# AuxSupply_USB.net
KiCad netlist of a schematic drawn in Altium Designer
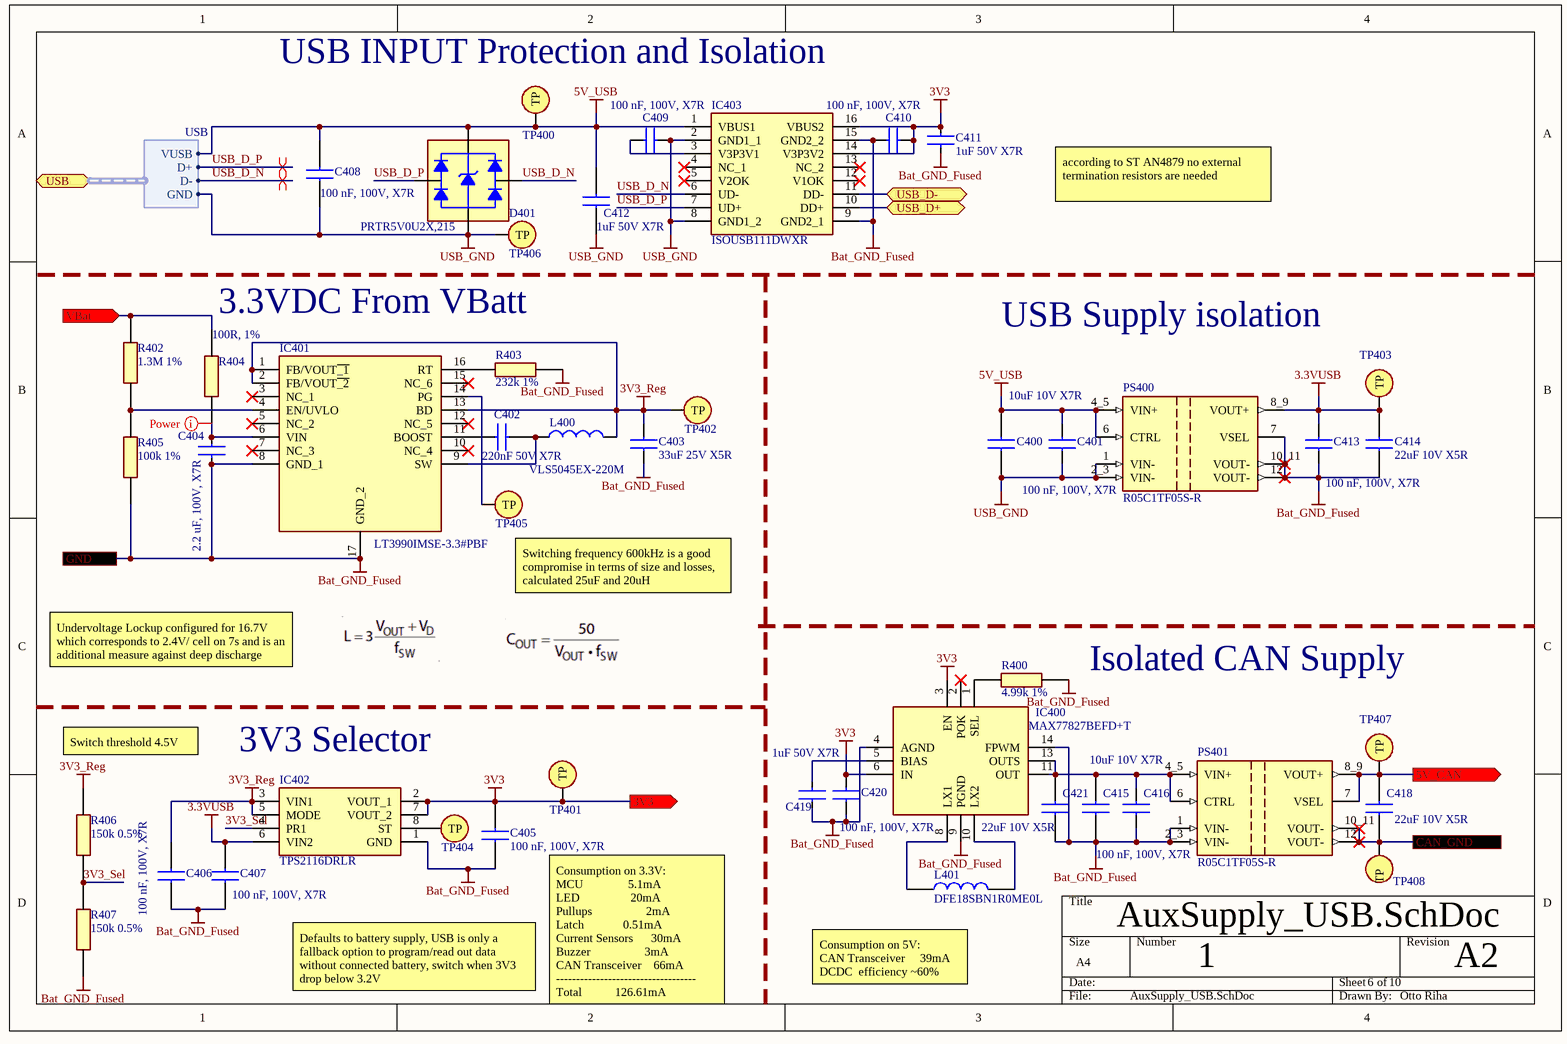
[diagram p0: AuxSupply_USB.SchDoc]

(export (version "E")
  (design (tool "Eeschema 10.0.6"))
  (components
    (comp (ref "C400")
      (value "10uF 10V X7R")
      (footprint "SamacSys:GRM18x")
      (description "Capacitor")
      (fields
        (field (name "MANUFACTURER_PART_NUMBER") "GRM188Z71A106MA73D")
        (field (name "MOUSER PART NUMBER") "81-GRM188Z71A106MA3D")
      )
      (libsource (lib "*") (part "GRM188Z71A106MA73D"))
    )
    (comp (ref "C401")
      (value "100 nF, 100V, X7R")
      (footprint "SamacSys:MAJx16")
      (description "Capacitor 100nF, 100V, X7R")
      (fields
        (field (name "MANUFACTURER_PART_NUMBER") "MAJCH168BB7104KTEA01")
        (field (name "MOUSER PART NUMBER") "963-MAJCH168BB7104KT")
      )
      (libsource (lib "SamacSys") (part "MAJCH168BB7104KTEA01"))
    )
    (comp (ref "C402")
      (value "220nF 50V X7R")
      (footprint "SamacSys:GRM18x")
      (description "Capacitor")
      (fields
        (field (name "MANUFACTURER_PART_NUMBER") "GRM188R71H224KAC4J")
        (field (name "MOUSER PART NUMBER") "81-GRM188R71H224KA4J")
      )
      (libsource (lib "*") (part "GRM188R71H224KAC4J"))
    )
    (comp (ref "C403")
      (value "33uF 25V X5R")
      (footprint "SamacSys:CAPC3216X180N")
      (description "Capacitor 33uF 25V X5R")
      (fields
        (field (name "MANUFACTURER_PART_NUMBER") "C3216X5R1E336M160AC")
        (field (name "MOUSER PART NUMBER") "810-C3216X5R1E336M")
      )
      (libsource (lib "SamacSys") (part "C3216X5R1E336M160AC"))
    )
    (comp (ref "C404")
      (value "2.2 uF, 100V, X7R")
      (footprint "SamacSys:CAPC2012X145N")
      (description "Capacitor 2.2 uF, 100V, X7R")
      (fields
        (field (name "MANUFACTURER_PART_NUMBER") "C2012X7R2A225K125AC")
        (field (name "MOUSER PART NUMBER") "810-C2012X7R2225K125")
      )
      (libsource (lib "SamacSys") (part "C2012X7R2A225K125AC"))
    )
    (comp (ref "C405")
      (value "100 nF, 100V, X7R")
      (footprint "SamacSys:MAJx16")
      (description "Capacitor 100nF, 100V, X7R")
      (fields
        (field (name "MANUFACTURER_PART_NUMBER") "MAJCH168BB7104KTEA01")
        (field (name "MOUSER PART NUMBER") "963-MAJCH168BB7104KT")
      )
      (libsource (lib "") (part "MAJCH168BB7104KTEA01_1"))
    )
    (comp (ref "C406")
      (value "100 nF, 100V, X7R")
      (footprint "SamacSys:MAJx16")
      (description "Capacitor 100nF, 100V, X7R")
      (fields
        (field (name "MANUFACTURER_PART_NUMBER") "MAJCH168BB7104KTEA01")
        (field (name "MOUSER PART NUMBER") "963-MAJCH168BB7104KT")
      )
      (libsource (lib "") (part "MAJCH168BB7104KTEA01_1"))
    )
    (comp (ref "C407")
      (value "100 nF, 100V, X7R")
      (footprint "SamacSys:MAJx16")
      (description "Capacitor 100nF, 100V, X7R")
      (fields
        (field (name "MANUFACTURER_PART_NUMBER") "MAJCH168BB7104KTEA01")
        (field (name "MOUSER PART NUMBER") "963-MAJCH168BB7104KT")
      )
      (libsource (lib "") (part "MAJCH168BB7104KTEA01_1"))
    )
    (comp (ref "C408")
      (value "100 nF, 100V, X7R")
      (footprint "SamacSys:MAJx16")
      (description "Capacitor 100nF, 100V, X7R")
      (fields
        (field (name "MANUFACTURER_PART_NUMBER") "MAJCH168BB7104KTEA01")
        (field (name "MOUSER PART NUMBER") "963-MAJCH168BB7104KT")
      )
      (libsource (lib "") (part "MAJCH168BB7104KTEA01_1"))
    )
    (comp (ref "C409")
      (value "100 nF, 100V, X7R")
      (footprint "SamacSys:MAJx16")
      (description "Capacitor 100nF, 100V, X7R")
      (fields
        (field (name "MANUFACTURER_PART_NUMBER") "MAJCH168BB7104KTEA01")
        (field (name "MOUSER PART NUMBER") "963-MAJCH168BB7104KT")
      )
      (libsource (lib "SamacSys") (part "MAJCH168BB7104KTEA01"))
    )
    (comp (ref "C410")
      (value "100 nF, 100V, X7R")
      (footprint "SamacSys:MAJx16")
      (description "Capacitor 100nF, 100V, X7R")
      (fields
        (field (name "MANUFACTURER_PART_NUMBER") "MAJCH168BB7104KTEA01")
        (field (name "MOUSER PART NUMBER") "963-MAJCH168BB7104KT")
      )
      (libsource (lib "SamacSys") (part "MAJCH168BB7104KTEA01"))
    )
    (comp (ref "C411")
      (value "1uF 50V X7R")
      (footprint "SamacSys:CAPC1608X90N")
      (description "Capacitor 1uF 50V X7R")
      (fields
        (field (name "MANUFACTURER_PART_NUMBER") "06035C105MAT2A")
        (field (name "MOUSER PART NUMBER") "581-06035C105MAT2A")
      )
      (libsource (lib "SamacSys") (part "06035C105MAT2A"))
    )
    (comp (ref "C412")
      (value "1uF 50V X7R")
      (footprint "SamacSys:CAPC1608X90N")
      (description "Capacitor 1uF 50V X7R")
      (fields
        (field (name "MANUFACTURER_PART_NUMBER") "06035C105MAT2A")
        (field (name "MOUSER PART NUMBER") "581-06035C105MAT2A")
      )
      (libsource (lib "") (part "06035C105MAT2A_1"))
    )
    (comp (ref "C413")
      (value "100 nF, 100V, X7R")
      (footprint "SamacSys:MAJx16")
      (description "Capacitor 100nF, 100V, X7R")
      (fields
        (field (name "MANUFACTURER_PART_NUMBER") "MAJCH168BB7104KTEA01")
        (field (name "MOUSER PART NUMBER") "963-MAJCH168BB7104KT")
      )
      (libsource (lib "SamacSys") (part "MAJCH168BB7104KTEA01"))
    )
    (comp (ref "C414")
      (value "22uF 10V X5R")
      (footprint "SamacSys:CAPC1608X105N")
      (description "Capacitor")
      (fields
        (field (name "MANUFACTURER_PART_NUMBER") "CL10A226MP8NUNE")
        (field (name "MOUSER PART NUMBER") "187-CL10A226MP8NUNE")
      )
      (libsource (lib "*") (part "CL10A226MP8NUNE"))
    )
    (comp (ref "C415")
      (value "10uF 10V X7R")
      (footprint "SamacSys:GRM18x")
      (description "Capacitor")
      (fields
        (field (name "MANUFACTURER_PART_NUMBER") "GRM188Z71A106MA73D")
        (field (name "MOUSER PART NUMBER") "81-GRM188Z71A106MA3D")
      )
      (libsource (lib "*") (part "GRM188Z71A106MA73D"))
    )
    (comp (ref "C416")
      (value "100 nF, 100V, X7R")
      (footprint "SamacSys:MAJx16")
      (description "Capacitor 100nF, 100V, X7R")
      (fields
        (field (name "MANUFACTURER_PART_NUMBER") "MAJCH168BB7104KTEA01")
        (field (name "MOUSER PART NUMBER") "963-MAJCH168BB7104KT")
      )
      (libsource (lib "SamacSys") (part "MAJCH168BB7104KTEA01"))
    )
    (comp (ref "C418")
      (value "22uF 10V X5R")
      (footprint "SamacSys:CAPC1608X105N")
      (description "Capacitor")
      (fields
        (field (name "MANUFACTURER_PART_NUMBER") "CL10A226MP8NUNE")
        (field (name "MOUSER PART NUMBER") "187-CL10A226MP8NUNE")
      )
      (libsource (lib "*") (part "CL10A226MP8NUNE"))
    )
    (comp (ref "C419")
      (value "1uF 50V X7R")
      (footprint "SamacSys:CAPC1608X90N")
      (description "Capacitor 1uF 50V X7R")
      (fields
        (field (name "MANUFACTURER_PART_NUMBER") "06035C105MAT2A")
        (field (name "MOUSER PART NUMBER") "581-06035C105MAT2A")
      )
      (libsource (lib "SamacSys") (part "06035C105MAT2A"))
    )
    (comp (ref "C420")
      (value "100 nF, 100V, X7R")
      (footprint "SamacSys:MAJx16")
      (description "Capacitor 100nF, 100V, X7R")
      (fields
        (field (name "MANUFACTURER_PART_NUMBER") "MAJCH168BB7104KTEA01")
        (field (name "MOUSER PART NUMBER") "963-MAJCH168BB7104KT")
      )
      (libsource (lib "SamacSys") (part "MAJCH168BB7104KTEA01"))
    )
    (comp (ref "C421")
      (value "22uF 10V X5R")
      (footprint "SamacSys:CAPC1608X105N")
      (description "Capacitor")
      (fields
        (field (name "MANUFACTURER_PART_NUMBER") "CL10A226MP8NUNE")
        (field (name "MOUSER PART NUMBER") "187-CL10A226MP8NUNE")
      )
      (libsource (lib "*") (part "CL10A226MP8NUNE"))
    )
    (comp (ref "D401")
      (value "PRTR5V0U2X,215")
      (footprint "SamacSys:PRTR5V0U2X")
      (description "Diode")
      (fields (field (name "MOUSER PART NUMBER") "771-PRTR5V0U2X-T/R"))
      (libsource (lib "SamacSys") (part "PRTR5V0U2X,215"))
    )
    (comp (ref "IC400")
      (value "MAX77827BEFD+T")
      (footprint "SamacSys:MAX77827BEFDT")
      (description "Integrated Circuit")
      (fields (field (name "MOUSER PART NUMBER") "700-MAX77827BEFD+T"))
      (libsource (lib "*") (part "MAX77827BEFD+T"))
    )
    (comp (ref "IC401")
      (value "LT3990IMSE-3.3#PBF")
      (footprint "SamacSys:SOP50P490X110-17N")
      (description "Integrated Circuit")
      (fields (field (name "MOUSER PART NUMBER") "584-3990IMSE-3.3PBF"))
      (libsource (lib "*") (part "LT3990IMSE-3.3#PBF"))
    )
    (comp (ref "IC402")
      (value "TPS2116DRLR")
      (footprint "SamacSys:SOTFL50P160X60-8N")
      (description "Integrated Circuit")
      (fields (field (name "MOUSER PART NUMBER") "595-TPS2116DRLR"))
      (libsource (lib "SamacSys") (part "TPS2116DRLR"))
    )
    (comp (ref "IC403")
      (value "ISOUSB111DWXR")
      (footprint "SamacSys:SOP65P1030X260-16N")
      (description "Integrated Circuit")
      (fields (field (name "MOUSER PART NUMBER") "595-ISOUSB111DWXR"))
      (libsource (lib "*") (part "ISOUSB111DWXR"))
    )
    (comp (ref "L400")
      (value "VLS5045EX-220M")
      (footprint "SamacSys:VLS5045EX330M")
      (description "Inductor")
      (fields (field (name "MOUSER PART NUMBER") "810-VLS5045EX-220M"))
      (libsource (lib "*") (part "VLS5045EX-220M"))
    )
    (comp (ref "L401")
      (value "DFE18SBN1R0ME0L")
      (footprint "SamacSys:DFE18SAN1R0ME0L")
      (description "Inductor")
      (fields (field (name "MOUSER PART NUMBER") "81-DFE18SBN1R0ME0L"))
      (libsource (lib "*") (part "DFE18SBN1R0ME0L"))
    )
    (comp (ref "PS400")
      (value "R05C1TF05S-R")
      (footprint "CONV_R05C1TF05S-R")
      (fields (field (name "MF") "{'manufacturer': u'Recom Power'}"))
      (libsource (lib "R05C1TF05S-R") (part "R05C1TF05S-R"))
    )
    (comp (ref "PS401")
      (value "R05C1TF05S-R")
      (footprint "CONV_R05C1TF05S-R")
      (fields (field (name "MF") "{'manufacturer': u'Recom Power'}"))
      (libsource (lib "R05C1TF05S-R") (part "R05C1TF05S-R"))
    )
    (comp (ref "R400")
      (value "4.99k 1%")
      (footprint "SamacSys:RESC0603X26N")
      (description "Resistor")
      (fields
        (field (name "MANUFACTURER_PART_NUMBER") "CR0201-FW-4991GLF")
        (field (name "MOUSER PART NUMBER") "652-CR0201FW-4991GLF")
      )
      (libsource (lib "*") (part "CR0201-FW-4991GLF"))
    )
    (comp (ref "R402")
      (value "1.3M 1%")
      (footprint "SamacSys:RESC1608X55N")
      (description "Resistor 1.3M 1%")
      (fields
        (field (name "MANUFACTURER_PART_NUMBER") "MCT0603MD1304BP500")
        (field (name "MOUSER PART NUMBER") "594-MCT0603MD1304BP5")
      )
      (libsource (lib "SamacSys") (part "MCT0603MD1304BP500"))
    )
    (comp (ref "R403")
      (value "232k 1%")
      (footprint "SamacSys:RESC1608X50N")
      (description "Resistor")
      (fields
        (field (name "MANUFACTURER_PART_NUMBER") "CRCW0603232KFKEA")
        (field (name "MOUSER PART NUMBER") "71-CRCW0603-232K-E3")
      )
      (libsource (lib "*") (part "CRCW0603232KFKEA"))
    )
    (comp (ref "R404")
      (value "100R, 1%")
      (footprint "SamacSys:RESC1608X50N")
      (description "Resistor 100R, 1%")
      (fields
        (field (name "MANUFACTURER_PART_NUMBER") "CRCW0603100RFKEA")
        (field (name "MOUSER PART NUMBER") "71-CRCW0603-100-E3")
      )
      (libsource (lib "SamacSys") (part "CRCW0603100RFKEA"))
    )
    (comp (ref "R405")
      (value "100k 1%")
      (footprint "SamacSys:RESC1608X55N")
      (description "Resistor 100k, 1%")
      (fields
        (field (name "MANUFACTURER_PART_NUMBER") "CRCW0603100KFKEAC")
        (field (name "MOUSER PART NUMBER") "71-CRCW0603100KFKEAC")
      )
      (libsource (lib "SamacSys") (part "CRCW0603100KFKEAC"))
    )
    (comp (ref "R406")
      (value "150k 0.5%")
      (footprint "SamacSys:ERA3AEB101V")
      (description "Resistor 150k 0.5%")
      (fields
        (field (name "MANUFACTURER_PART_NUMBER") "ERA-3AED154V")
        (field (name "MOUSER PART NUMBER") "667-ERA-3AED154V")
      )
      (libsource (lib "SamacSys") (part "ERA-3AED154V"))
    )
    (comp (ref "R407")
      (value "150k 0.5%")
      (footprint "SamacSys:ERA3AEB101V")
      (description "Resistor 150k 0.5%")
      (fields
        (field (name "MANUFACTURER_PART_NUMBER") "ERA-3AED154V")
        (field (name "MOUSER PART NUMBER") "667-ERA-3AED154V")
      )
      (libsource (lib "SamacSys") (part "ERA-3AED154V"))
    )
    (comp (ref "TP400")
      (value "Testpoint")
      (footprint "Testpoint")
      (libsource (lib "SamacSys") (part "Testpoint"))
    )
    (comp (ref "TP401")
      (value "Testpoint")
      (footprint "Testpoint")
      (libsource (lib "SamacSys") (part "Testpoint"))
    )
    (comp (ref "TP402")
      (value "Testpoint")
      (footprint "Testpoint")
      (libsource (lib "SamacSys") (part "Testpoint"))
    )
    (comp (ref "TP403")
      (value "Testpoint")
      (footprint "Testpoint")
      (libsource (lib "SamacSys") (part "Testpoint"))
    )
    (comp (ref "TP404")
      (value "Testpoint")
      (footprint "Testpoint")
      (libsource (lib "SamacSys") (part "Testpoint"))
    )
    (comp (ref "TP405")
      (value "Testpoint")
      (footprint "Testpoint")
      (libsource (lib "SamacSys") (part "Testpoint"))
    )
    (comp (ref "TP406")
      (value "Testpoint")
      (footprint "Testpoint")
      (libsource (lib "SamacSys") (part "Testpoint"))
    )
    (comp (ref "TP407")
      (value "Testpoint")
      (footprint "Testpoint")
      (libsource (lib "SamacSys") (part "Testpoint"))
    )
    (comp (ref "TP408")
      (value "Testpoint")
      (footprint "Testpoint")
      (libsource (lib "SamacSys") (part "Testpoint"))
    )
  )
  (nets
    (net (code "2") (name "/3V3_Sel") (class "Default")
      (node (ref "IC402") (pin "4") (pinfunction "PR1_4") (pintype "passive"))
      (node (ref "R406") (pin "1") (pinfunction "1_1") (pintype "passive"))
      (node (ref "R407") (pin "2") (pinfunction "2_2") (pintype "passive"))
    )
    (net (code "3") (name "/5V_CAN") (class "Default")
      (node (ref "C418") (pin "2") (pinfunction "2_2") (pintype "passive"))
      (node (ref "PS401") (pin "7") (pinfunction "VSEL_7") (pintype "passive"))
      (node (ref "PS401") (pin "8_9") (pinfunction "VOUT+_8_9") (pintype "output"))
      (node (ref "TP407") (pin "1") (pinfunction "TP_1") (pintype "passive"))
    )
    (net (code "4") (name "/CAN_GND") (class "Default")
      (node (ref "C418") (pin "1") (pinfunction "1_1") (pintype "passive"))
      (node (ref "PS401") (pin "10_11") (pinfunction "VOUT-_10_11") (pintype "output"))
      (node (ref "PS401") (pin "12") (pinfunction "VOUT-_12") (pintype "output"))
      (node (ref "TP408") (pin "1") (pinfunction "TP_1") (pintype "passive"))
    )
    (net (code "5") (name "/USB_D+") (class "Default")
      (node (ref "IC403") (pin "10") (pinfunction "DD+_10") (pintype "passive"))
    )
    (net (code "6") (name "/USB_D-") (class "Default")
      (node (ref "IC403") (pin "11") (pinfunction "DD-_11") (pintype "passive"))
    )
    (net (code "7") (name "/USB_D_N") (class "Default")
      (node (ref "D401") (pin "3") (pinfunction "input/output_2_3") (pintype "passive"))
      (node (ref "IC403") (pin "6") (pinfunction "UD-_6") (pintype "passive"))
    )
    (net (code "8") (name "/USB_D_P") (class "Default")
      (node (ref "D401") (pin "2") (pinfunction "input/output_1_2") (pintype "passive"))
      (node (ref "IC403") (pin "7") (pinfunction "UD+_7") (pintype "passive"))
    )
    (net (code "9") (name "/VBat") (class "Default")
      (node (ref "R402") (pin "2") (pinfunction "2_2") (pintype "passive"))
      (node (ref "R404") (pin "2") (pinfunction "2_2") (pintype "passive"))
    )
    (net (code "11") (name "3.3VUSB") (class "Default")
      (node (ref "C407") (pin "2") (pinfunction "2_2") (pintype "passive"))
      (node (ref "C413") (pin "1") (pinfunction "1_1") (pintype "passive"))
      (node (ref "C414") (pin "2") (pinfunction "2_2") (pintype "passive"))
      (node (ref "IC402") (pin "6") (pinfunction "VIN2_6") (pintype "passive"))
      (node (ref "PS400") (pin "8_9") (pinfunction "VOUT+_8_9") (pintype "output"))
      (node (ref "TP403") (pin "1") (pinfunction "TP_1") (pintype "passive"))
    )
    (net (code "12") (name "3V3") (class "Default")
      (node (ref "C405") (pin "2") (pinfunction "2_2") (pintype "passive"))
      (node (ref "C410") (pin "1") (pinfunction "1_1") (pintype "passive"))
      (node (ref "C411") (pin "2") (pinfunction "2_2") (pintype "passive"))
      (node (ref "C420") (pin "1") (pinfunction "1_1") (pintype "passive"))
      (node (ref "IC400") (pin "3") (pinfunction "EN_3") (pintype "passive"))
      (node (ref "IC400") (pin "6") (pinfunction "IN_6") (pintype "passive"))
      (node (ref "IC402") (pin "2") (pinfunction "VOUT_1_2") (pintype "passive"))
      (node (ref "IC402") (pin "7") (pinfunction "VOUT_2_7") (pintype "passive"))
      (node (ref "IC403") (pin "14") (pinfunction "V3P3V2_14") (pintype "passive"))
      (node (ref "IC403") (pin "16") (pinfunction "VBUS2_16") (pintype "passive"))
      (node (ref "TP401") (pin "1") (pinfunction "TP_1") (pintype "passive"))
    )
    (net (code "13") (name "3V3_Reg") (class "Default")
      (node (ref "C403") (pin "2") (pinfunction "2_2") (pintype "passive"))
      (node (ref "C406") (pin "2") (pinfunction "2_2") (pintype "passive"))
      (node (ref "IC401") (pin "1") (pinfunction "FB/VOUT~{_1}_1") (pintype "passive"))
      (node (ref "IC401") (pin "13") (pinfunction "BD_13") (pintype "passive"))
      (node (ref "IC401") (pin "2") (pinfunction "FB/VOUT~{_2}_2") (pintype "passive"))
      (node (ref "IC402") (pin "3") (pinfunction "VIN1_3") (pintype "passive"))
      (node (ref "IC402") (pin "5") (pinfunction "MODE_5") (pintype "passive"))
      (node (ref "L400") (pin "2") (pinfunction "2_2") (pintype "passive"))
      (node (ref "R406") (pin "2") (pinfunction "2_2") (pintype "passive"))
      (node (ref "TP402") (pin "1") (pinfunction "TP_1") (pintype "passive"))
    )
    (net (code "14") (name "5V_USB") (class "Default")
      (node (ref "C400") (pin "2") (pinfunction "2_2") (pintype "passive"))
      (node (ref "C401") (pin "1") (pinfunction "1_1") (pintype "passive"))
      (node (ref "C408") (pin "2") (pinfunction "2_2") (pintype "passive"))
      (node (ref "C412") (pin "1") (pinfunction "1_1") (pintype "passive"))
      (node (ref "D401") (pin "4") (pinfunction "supply_voltage_4") (pintype "passive"))
      (node (ref "IC403") (pin "1") (pinfunction "VBUS1_1") (pintype "passive"))
      (node (ref "PS400") (pin "4_5") (pinfunction "VIN+_4_5") (pintype "input"))
      (node (ref "PS400") (pin "6") (pinfunction "CTRL_6") (pintype "input"))
      (node (ref "TP400") (pin "1") (pinfunction "TP_1") (pintype "passive"))
    )
    (net (code "15") (name "Bat_GND_Fused") (class "Default")
      (node (ref "C403") (pin "1") (pinfunction "1_1") (pintype "passive"))
      (node (ref "C404") (pin "1") (pinfunction "1_1") (pintype "passive"))
      (node (ref "C405") (pin "1") (pinfunction "1_1") (pintype "passive"))
      (node (ref "C406") (pin "1") (pinfunction "1_1") (pintype "passive"))
      (node (ref "C407") (pin "1") (pinfunction "1_1") (pintype "passive"))
      (node (ref "C410") (pin "2") (pinfunction "2_2") (pintype "passive"))
      (node (ref "C411") (pin "1") (pinfunction "1_1") (pintype "passive"))
      (node (ref "C413") (pin "2") (pinfunction "2_2") (pintype "passive"))
      (node (ref "C414") (pin "1") (pinfunction "1_1") (pintype "passive"))
      (node (ref "C415") (pin "1") (pinfunction "1_1") (pintype "passive"))
      (node (ref "C416") (pin "2") (pinfunction "2_2") (pintype "passive"))
      (node (ref "C419") (pin "1") (pinfunction "1_1") (pintype "passive"))
      (node (ref "C420") (pin "2") (pinfunction "2_2") (pintype "passive"))
      (node (ref "C421") (pin "1") (pinfunction "1_1") (pintype "passive"))
      (node (ref "IC400") (pin "14") (pinfunction "FPWM_14") (pintype "passive"))
      (node (ref "IC400") (pin "4") (pinfunction "AGND_4") (pintype "passive"))
      (node (ref "IC400") (pin "9") (pinfunction "PGND_9") (pintype "passive"))
      (node (ref "IC401") (pin "17") (pinfunction "GND_2_17") (pintype "passive"))
      (node (ref "IC401") (pin "8") (pinfunction "GND_1_8") (pintype "passive"))
      (node (ref "IC402") (pin "1") (pinfunction "GND_1") (pintype "passive"))
      (node (ref "IC403") (pin "15") (pinfunction "GND2_2_15") (pintype "passive"))
      (node (ref "IC403") (pin "9") (pinfunction "GND2_1_9") (pintype "passive"))
      (node (ref "PS400") (pin "10_11") (pinfunction "VOUT-_10_11") (pintype "output"))
      (node (ref "PS400") (pin "12") (pinfunction "VOUT-_12") (pintype "output"))
      (node (ref "PS400") (pin "7") (pinfunction "VSEL_7") (pintype "passive"))
      (node (ref "PS401") (pin "1") (pinfunction "VIN-_1") (pintype "input"))
      (node (ref "PS401") (pin "2_3") (pinfunction "VIN-_2_3") (pintype "input"))
      (node (ref "R400") (pin "2") (pinfunction "2_2") (pintype "passive"))
      (node (ref "R403") (pin "2") (pinfunction "2_2") (pintype "passive"))
      (node (ref "R405") (pin "1") (pinfunction "1_1") (pintype "passive"))
      (node (ref "R407") (pin "1") (pinfunction "1_1") (pintype "passive"))
    )
    (net (code "16") (name "Net-(IC400-BIAS)") (class "Default")
      (node (ref "C419") (pin "2") (pinfunction "2_2") (pintype "passive"))
      (node (ref "IC400") (pin "5") (pinfunction "BIAS_5") (pintype "passive"))
    )
    (net (code "17") (name "Net-(IC400-LX1)") (class "Default")
      (node (ref "IC400") (pin "8") (pinfunction "LX1_8") (pintype "passive"))
      (node (ref "L401") (pin "1") (pinfunction "1_1") (pintype "passive"))
    )
    (net (code "18") (name "Net-(IC400-LX2)") (class "Default")
      (node (ref "IC400") (pin "10") (pinfunction "LX2_10") (pintype "passive"))
      (node (ref "L401") (pin "2") (pinfunction "2_2") (pintype "passive"))
    )
    (net (code "19") (name "Net-(IC400-OUT)") (class "Default")
      (node (ref "C415") (pin "2") (pinfunction "2_2") (pintype "passive"))
      (node (ref "C416") (pin "1") (pinfunction "1_1") (pintype "passive"))
      (node (ref "C421") (pin "2") (pinfunction "2_2") (pintype "passive"))
      (node (ref "IC400") (pin "11") (pinfunction "OUT_11") (pintype "passive"))
      (node (ref "IC400") (pin "13") (pinfunction "OUTS_13") (pintype "passive"))
      (node (ref "PS401") (pin "4_5") (pinfunction "VIN+_4_5") (pintype "input"))
      (node (ref "PS401") (pin "6") (pinfunction "CTRL_6") (pintype "input"))
    )
    (net (code "20") (name "Net-(IC400-SEL)") (class "Default")
      (node (ref "IC400") (pin "1") (pinfunction "SEL_1") (pintype "passive"))
      (node (ref "R400") (pin "1") (pinfunction "1_1") (pintype "passive"))
    )
    (net (code "21") (name "Net-(IC401-BOOST)") (class "Default")
      (node (ref "C402") (pin "1") (pinfunction "1_1") (pintype "passive"))
      (node (ref "IC401") (pin "11") (pinfunction "BOOST_11") (pintype "passive"))
    )
    (net (code "22") (name "Net-(IC401-EN{slash}UVLO)") (class "Default")
      (node (ref "IC401") (pin "4") (pinfunction "EN/UVLO_4") (pintype "passive"))
      (node (ref "R402") (pin "1") (pinfunction "1_1") (pintype "passive"))
      (node (ref "R405") (pin "2") (pinfunction "2_2") (pintype "passive"))
    )
    (net (code "23") (name "Net-(IC401-PG)") (class "Default")
      (node (ref "IC401") (pin "14") (pinfunction "PG_14") (pintype "passive"))
      (node (ref "TP405") (pin "1") (pinfunction "TP_1") (pintype "passive"))
    )
    (net (code "24") (name "Net-(IC401-RT)") (class "Default")
      (node (ref "IC401") (pin "16") (pinfunction "RT_16") (pintype "passive"))
      (node (ref "R403") (pin "1") (pinfunction "1_1") (pintype "passive"))
    )
    (net (code "25") (name "Net-(IC401-SW)") (class "Default")
      (node (ref "C402") (pin "2") (pinfunction "2_2") (pintype "passive"))
      (node (ref "IC401") (pin "9") (pinfunction "SW_9") (pintype "passive"))
      (node (ref "L400") (pin "1") (pinfunction "1_1") (pintype "passive"))
    )
    (net (code "26") (name "Net-(IC401-VIN)") (class "Default")
      (node (ref "C404") (pin "2") (pinfunction "2_2") (pintype "passive"))
      (node (ref "IC401") (pin "6") (pinfunction "VIN_6") (pintype "passive"))
      (node (ref "R404") (pin "1") (pinfunction "1_1") (pintype "passive"))
    )
    (net (code "27") (name "Net-(IC402-ST)") (class "Default")
      (node (ref "IC402") (pin "8") (pinfunction "ST_8") (pintype "passive"))
      (node (ref "TP404") (pin "1") (pinfunction "TP_1") (pintype "passive"))
    )
    (net (code "28") (name "Net-(IC403-V3P3V1)") (class "Default")
      (node (ref "C409") (pin "2") (pinfunction "2_2") (pintype "passive"))
      (node (ref "IC403") (pin "3") (pinfunction "V3P3V1_3") (pintype "passive"))
    )
    (net (code "29") (name "USB_GND") (class "Default")
      (node (ref "C400") (pin "1") (pinfunction "1_1") (pintype "passive"))
      (node (ref "C401") (pin "2") (pinfunction "2_2") (pintype "passive"))
      (node (ref "C408") (pin "1") (pinfunction "1_1") (pintype "passive"))
      (node (ref "C409") (pin "1") (pinfunction "1_1") (pintype "passive"))
      (node (ref "C412") (pin "2") (pinfunction "2_2") (pintype "passive"))
      (node (ref "D401") (pin "1") (pinfunction "ground_1") (pintype "passive"))
      (node (ref "IC403") (pin "2") (pinfunction "GND1_1_2") (pintype "passive"))
      (node (ref "IC403") (pin "8") (pinfunction "GND1_2_8") (pintype "passive"))
      (node (ref "PS400") (pin "1") (pinfunction "VIN-_1") (pintype "input"))
      (node (ref "PS400") (pin "2_3") (pinfunction "VIN-_2_3") (pintype "input"))
      (node (ref "TP406") (pin "1") (pinfunction "TP_1") (pintype "passive"))
    )
    (net (code "30") (name "unconnected-(IC400-POK-Pad2)") (class "Default")
      (node (ref "IC400") (pin "2") (pinfunction "POK_2") (pintype "passive+no_connect"))
    )
    (net (code "31") (name "unconnected-(IC401-NC_1-Pad3)") (class "Default")
      (node (ref "IC401") (pin "3") (pinfunction "NC_1_3") (pintype "passive+no_connect"))
    )
    (net (code "32") (name "unconnected-(IC401-NC_2-Pad5)") (class "Default")
      (node (ref "IC401") (pin "5") (pinfunction "NC_2_5") (pintype "passive+no_connect"))
    )
    (net (code "33") (name "unconnected-(IC401-NC_3-Pad7)") (class "Default")
      (node (ref "IC401") (pin "7") (pinfunction "NC_3_7") (pintype "passive+no_connect"))
    )
    (net (code "34") (name "unconnected-(IC401-NC_4-Pad10)") (class "Default")
      (node (ref "IC401") (pin "10") (pinfunction "NC_4_10") (pintype "passive+no_connect"))
    )
    (net (code "35") (name "unconnected-(IC401-NC_5-Pad12)") (class "Default")
      (node (ref "IC401") (pin "12") (pinfunction "NC_5_12") (pintype "passive+no_connect"))
    )
    (net (code "36") (name "unconnected-(IC401-NC_6-Pad15)") (class "Default")
      (node (ref "IC401") (pin "15") (pinfunction "NC_6_15") (pintype "passive+no_connect"))
    )
    (net (code "37") (name "unconnected-(IC403-NC_1-Pad4)") (class "Default")
      (node (ref "IC403") (pin "4") (pinfunction "NC_1_4") (pintype "passive+no_connect"))
    )
    (net (code "38") (name "unconnected-(IC403-NC_2-Pad13)") (class "Default")
      (node (ref "IC403") (pin "13") (pinfunction "NC_2_13") (pintype "passive+no_connect"))
    )
    (net (code "39") (name "unconnected-(IC403-V1OK-Pad12)") (class "Default")
      (node (ref "IC403") (pin "12") (pinfunction "V1OK_12") (pintype "passive+no_connect"))
    )
    (net (code "40") (name "unconnected-(IC403-V2OK-Pad5)") (class "Default")
      (node (ref "IC403") (pin "5") (pinfunction "V2OK_5") (pintype "passive+no_connect"))
    )
  )
)
